# Sheet2.net
KiCad netlist of a schematic drawn in Altium Designer
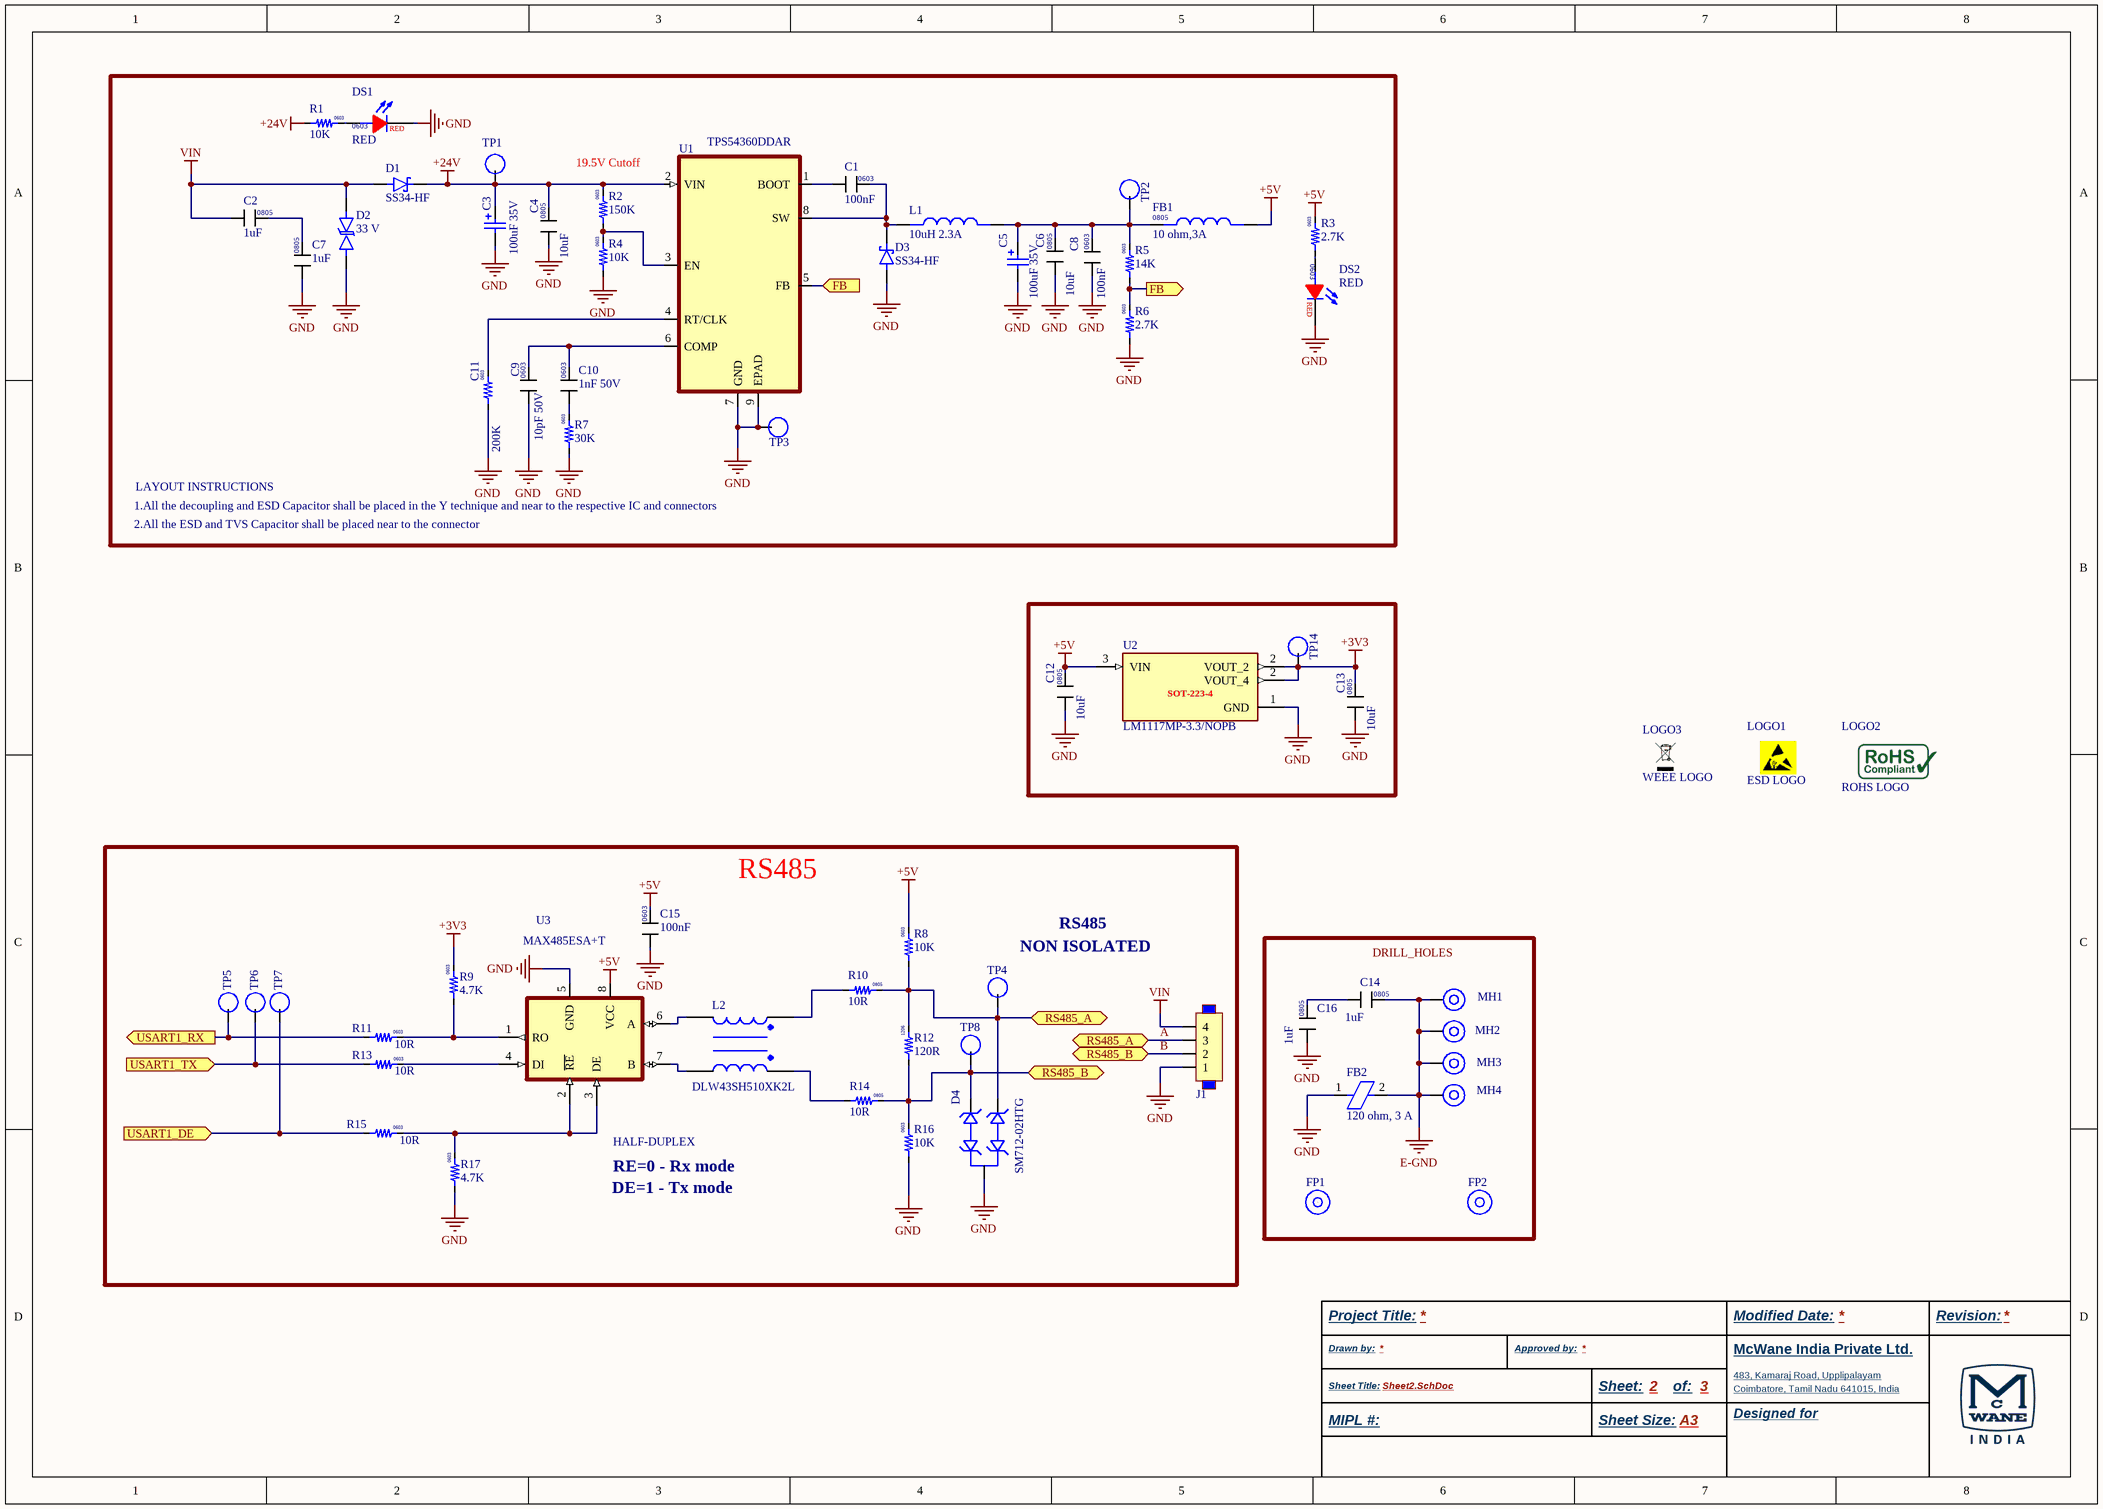
[diagram p0: Sheet2.SchDoc]

(export (version "E")
  (design (tool "Eeschema 10.0.6"))
  (components
    (comp (ref "C1")
      (value "100nF")
      (footprint "CAP_0603")
      (description "SMD Multilayer Ceramic Capacitor, 0.1 µF, 50 V, 0603 [1608 Metric], ± 10%, X7R")
      (fields
        (field (name "MANUFACTURER PART NUMBER") "CC0603KRX7R9BB104")
        (field (name "LCSC PART") "C14663")
      )
      (libsource (lib "Passive_Components") (part "C0603-0.1uF 50V-MLCC"))
    )
    (comp (ref "C2")
      (value "1uF")
      (footprint "CAP_0805")
      (description "SMD Multilayer Ceramic Capacitor, 1 µF, 50 V, 0805 [2012 Metric], ± 10%, X7R, -55 °C")
      (fields
        (field (name "MANUFACTURER PART NUMBER") "CC0805KKX7R9BB105")
        (field (name "LCSC PART") "C91185")
      )
      (libsource (lib "Passive_Components") (part "C0805-1uF 50V-MLCC"))
    )
    (comp (ref "C3")
      (value "100uF 35V")
      (footprint "CAP_ELE_AL_6.3X7.7")
      (description "SMD Aluminium Electrolytic Capacitor, Radial Can - SMD, 100 µF, 35 V, 2000 hours @ 105°C, Polar")
      (fields (field (name "MANUFACTURER PART NUMBER") "MCVVT035M101EA6L"))
      (libsource (lib "Passive_Components") (part "CAP_SMD_100uF_35V"))
    )
    (comp (ref "C4")
      (value "10uF")
      (footprint "CAP_0805")
      (description "SMD Multilayer Ceramic Capacitor, 10 µF, 50 V, 0805 [2012 Metric], ± 10%, X5R")
      (fields
        (field (name "MANUFACTURER PART NUMBER") "CC0805KKX5R9BB106")
        (field (name "LCSC PART") "C440198")
      )
      (libsource (lib "Passive_Components") (part "C0805-10uF 50V-MLCC"))
    )
    (comp (ref "C5")
      (value "100uF 35V")
      (footprint "CAP_ELE_AL_6.3X7.7")
      (description "SMD Aluminium Electrolytic Capacitor, Radial Can - SMD, 100 µF, 35 V, 2000 hours @ 105°C, Polar")
      (fields (field (name "MANUFACTURER PART NUMBER") "MCVVT035M101EA6L"))
      (libsource (lib "Passive_Components") (part "CAP_SMD_100uF_35V"))
    )
    (comp (ref "C6")
      (value "10uF")
      (footprint "CAP_0805")
      (description "SMD Multilayer Ceramic Capacitor, 10 µF, 50 V, 0805 [2012 Metric], ± 10%, X5R")
      (fields
        (field (name "MANUFACTURER PART NUMBER") "CC0805KKX5R9BB106")
        (field (name "LCSC PART") "C440198")
      )
      (libsource (lib "Passive_Components") (part "C0805-10uF 50V-MLCC"))
    )
    (comp (ref "C7")
      (value "1uF")
      (footprint "CAP_0805")
      (description "SMD Multilayer Ceramic Capacitor, 1 µF, 50 V, 0805 [2012 Metric], ± 10%, X7R, -55 °C")
      (fields
        (field (name "MANUFACTURER PART NUMBER") "CC0805KKX7R9BB105")
        (field (name "LCSC PART") "C91185")
      )
      (libsource (lib "Passive_Components") (part "C0805-1uF 50V-MLCC"))
    )
    (comp (ref "C8")
      (value "100nF")
      (footprint "CAP_0603")
      (description "SMD Multilayer Ceramic Capacitor, 0.1 µF, 50 V, 0603 [1608 Metric], ± 10%, X7R")
      (fields
        (field (name "MANUFACTURER PART NUMBER") "CC0603KRX7R9BB104")
        (field (name "LCSC PART") "C14663")
      )
      (libsource (lib "Passive_Components") (part "C0603-0.1uF 50V-MLCC"))
    )
    (comp (ref "C9")
      (value "10pF 50V")
      (footprint "CAP_0603")
      (description "SMD Multilayer Ceramic Capacitor, 10 pF, 50 V, 0603 [1608 Metric], ± 10%, C0G / NP0, -55 °C")
      (fields (field (name "MANUFACTURER PART NUMBER") "CC0603KRNPO9BN100"))
      (libsource (lib "Passive_Components") (part "C0603-10pF 50V-MLCC"))
    )
    (comp (ref "C10")
      (value "1nF 50V")
      (footprint "CAP_0603")
      (description "SMD Multilayer Ceramic Capacitor, 1 nF, 50 V, 0603 [1608 Metric], ± 10%, X7R")
      (fields (field (name "MANUFACTURER PART NUMBER") "CC0603KRX7R9BB102"))
      (libsource (lib "Passive_Components") (part "C0603-1nF 50V-MLCC"))
    )
    (comp (ref "C11")
      (value "200K")
      (footprint "RES_0603")
      (description "SMD Chip Resistor, 200 kohm, ± 1%, 100 mW, 0603 [1608 Metric], Thick Film, General Purpose")
      (fields (field (name "MANUFACTURER PART NUMBER") "RC0603FR-07200KL"))
      (libsource (lib "Passive_Components") (part "R0603-200K-1%"))
    )
    (comp (ref "C12")
      (value "10uF")
      (footprint "CAP_0805")
      (description "SMD Multilayer Ceramic Capacitor, 10 µF, 50 V, 0805 [2012 Metric], ± 10%, X5R")
      (fields
        (field (name "MANUFACTURER PART NUMBER") "CC0805KKX5R9BB106")
        (field (name "LCSC PART") "C440198")
      )
      (libsource (lib "Passive_Components") (part "C0805-10uF 50V-MLCC"))
    )
    (comp (ref "C13")
      (value "10uF")
      (footprint "CAP_0805")
      (description "SMD Multilayer Ceramic Capacitor, 10 µF, 50 V, 0805 [2012 Metric], ± 10%, X5R")
      (fields
        (field (name "MANUFACTURER PART NUMBER") "CC0805KKX5R9BB106")
        (field (name "LCSC PART") "C440198")
      )
      (libsource (lib "Passive_Components") (part "C0805-10uF 50V-MLCC"))
    )
    (comp (ref "C14")
      (value "1uF")
      (footprint "CAP_0805")
      (description "SMD Multilayer Ceramic Capacitor, 1 µF, 50 V, 0805 [2012 Metric], ± 10%, X7R, -55 °C")
      (fields
        (field (name "MANUFACTURER PART NUMBER") "CC0805KKX7R9BB105")
        (field (name "LCSC PART") "C91185")
      )
      (libsource (lib "Passive_Components") (part "C0805-1uF 50V-MLCC"))
    )
    (comp (ref "C15")
      (value "100nF")
      (footprint "CAP_0603")
      (description "SMD Multilayer Ceramic Capacitor, 0.1 µF, 50 V, 0603 [1608 Metric], ± 10%, X7R")
      (fields
        (field (name "MANUFACTURER PART NUMBER") "CC0603KRX7R9BB104")
        (field (name "LCSC PART") "C14663")
      )
      (libsource (lib "Passive_Components") (part "C0603-0.1uF 50V-MLCC"))
    )
    (comp (ref "C16")
      (value "1uF")
      (footprint "CAP_0805")
      (description "SMD Multilayer Ceramic Capacitor, 1 µF, 50 V, 0805 [2012 Metric], ± 10%, X7R, -55 °C")
      (fields
        (field (name "MANUFACTURER PART NUMBER") "CC0805KKX7R9BB105")
        (field (name "LCSC PART") "C91185")
      )
      (libsource (lib "Passive_Components") (part "C0805-1uF 50V-MLCC"))
    )
    (comp (ref "D1")
      (value "SS34-HF")
      (footprint "Diode_SMA_DO-214AC")
      (description "Schottky Rectifier, SSxx Series, 40 V, 3 A, Single, DO-214AC (SMA), 2 Pins, 500 mV")
      (libsource (lib "Active_Components") (part "SS34-HF"))
    )
    (comp (ref "D2")
      (value "33 V")
      (footprint "Diode_SMA_DO-214AC")
      (description "TVS Diode, TRANSZORB SMAJ, Bidirectional, 33 V, 53.3 V, DO-214AC (SMA), 2 Pins")
      (fields (field (name "MANUFACTURER PART NUMBER") "SMAJ33CAHE3_A/H"))
      (libsource (lib "Active_Components") (part "SMAJ33CAHE3_A/H_1"))
    )
    (comp (ref "D3")
      (value "SS34-HF")
      (footprint "Diode_SMA_DO-214AC")
      (description "Schottky Rectifier, SSxx Series, 40 V, 3 A, Single, DO-214AC (SMA), 2 Pins, 500 mV")
      (libsource (lib "Active_Components") (part "SS34-HF"))
    )
    (comp (ref "D4")
      (value "SM712-02HTG")
      (footprint "SOT23")
      (description "ESD Protection Device, 31 V, SOT-23, 3 Pins, 12 V, 600 W, SPA SM712")
      (libsource (lib "Active_Components") (part "ESD_RS485_SM712"))
    )
    (comp (ref "DS1")
      (value "RED")
      (footprint "LED_0603")
      (description "Red LED Indication - Discrete 1.95V 0603 (1608 Metric)")
      (fields
        (field (name "MANUFACTURER PART NUMBER") "19-217/R6C-AL1M2VY/3T")
        (field (name "LCSC PART") "C72044")
      )
      (libsource (lib "Active_Components") (part "19-217/R6C-AL1M2VY/3T"))
    )
    (comp (ref "DS2")
      (value "RED")
      (footprint "LED_0603")
      (description "Red LED Indication - Discrete 1.95V 0603 (1608 Metric)")
      (fields
        (field (name "MANUFACTURER PART NUMBER") "19-217/R6C-AL1M2VY/3T")
        (field (name "LCSC PART") "C72044")
      )
      (libsource (lib "Active_Components") (part "19-217/R6C-AL1M2VY/3T"))
    )
    (comp (ref "FB1")
      (value "10 ohm,3A")
      (footprint "IND_0805")
      (description "10 Ohms @ 100 MHz 1 Signal Line Ferrite Bead 0805 (2012 Metric) 3A 25mOhm")
      (fields (field (name "MANUFACTURER PART NUMBER") "742792011"))
      (libsource (lib "Passive_Components") (part "IND_0805"))
    )
    (comp (ref "FB2")
      (value "120 ohm, 3 A")
      (footprint "IND_1206")
      (description "Ferrite Bead, 1206 [3216 Metric], 120 ohm, 3 A, WE-CBF, 0.03 ohm, ± 25%")
      (fields (field (name "MANUFACTURER PART NUMBER") "742792113"))
      (libsource (lib "Passive_Components") (part "742792113"))
    )
    (comp (ref "FP1")
      (value "Fiducial_Point")
      (footprint "Fiducial_Point")
      (libsource (lib "CONNECTOR") (part "Fiducial_Point"))
    )
    (comp (ref "FP2")
      (value "Fiducial_Point")
      (footprint "Fiducial_Point")
      (libsource (lib "CONNECTOR") (part "Fiducial_Point"))
    )
    (comp (ref "J1")
      (value "WAGO250 104")
      (footprint "WAGO250_104")
      (description "4 Position Wire to Board Terminal Block 45° (135°) Angle with Board 0.138\" (3.50mm) Through Hole")
      (fields (field (name "MANUFACTURER PART NUMBER") "250-104/000-012"))
      (libsource (lib "CONNECTOR") (part "WAGO250_104"))
    )
    (comp (ref "L1")
      (value "10uH 2.3A")
      (footprint "IND_SMD_7X7X5")
      (description "10 µH Unshielded Inductor 2.3 A 70mOhm Max Nonstandard")
      (fields (field (name "MANUFACTURER PART NUMBER") "CD75NP-100KC") (field (name "LCSC PART") "C2454030"))
      (libsource (lib "Passive_Components") (part "IND_10uH_2.3A"))
    )
    (comp (ref "L2")
      (value "DLW43SH510XK2L")
      (footprint "IND_CMC_SMD_4.5X3.2X2.6mm")
      (description "51 µH @ 1 MHz 2 Line Common Mode Choke Surface Mount 230mA DCR 1Ohm")
      (libsource (lib "Passive_Components") (part "DLW43SH510XK2L"))
    )
    (comp (ref "LOGO1")
      (value "ESD LOGO")
      (footprint "ESD_LOGO")
      (libsource (lib "CONNECTOR") (part "ESD_LOGO"))
    )
    (comp (ref "LOGO2")
      (value "ROHS LOGO")
      (footprint "ROHS_LOGO")
      (libsource (lib "CONNECTOR") (part "ROHS_LOGO"))
    )
    (comp (ref "LOGO3")
      (value "WEEE LOGO")
      (footprint "EWASTE_LOGO")
      (libsource (lib "CONNECTOR") (part "WEEE_LOGO"))
    )
    (comp (ref "MH1")
      (value "MOUNT_HOLE_4mm")
      (footprint "MOUNT_HOLE_4mm")
      (libsource (lib "CONNECTOR") (part "MOUNT_HOLE_4mm"))
    )
    (comp (ref "MH2")
      (value "MOUNT_HOLE_4mm")
      (footprint "MOUNT_HOLE_4mm")
      (libsource (lib "CONNECTOR") (part "MOUNT_HOLE_4mm"))
    )
    (comp (ref "MH3")
      (value "MOUNT_HOLE_4mm")
      (footprint "MOUNT_HOLE_4mm")
      (libsource (lib "CONNECTOR") (part "MOUNT_HOLE_4mm"))
    )
    (comp (ref "MH4")
      (value "MOUNT_HOLE_4mm")
      (footprint "MOUNT_HOLE_4mm")
      (libsource (lib "CONNECTOR") (part "MOUNT_HOLE_4mm"))
    )
    (comp (ref "R1")
      (value "10K")
      (footprint "RES_0603")
      (description "SMD Chip Resistor, 10 kohm, ± 1%, 100 mW, 0603 [1608 Metric], Thick Film, General Purpose")
      (fields (field (name "MANUFACTURER PART NUMBER") "RC0603FR-0710KL") (field (name "LCSC PART") "C98220"))
      (libsource (lib "Passive_Components") (part "R0603-10K-1%"))
    )
    (comp (ref "R2")
      (value "150K")
      (footprint "RES_0603")
      (description "SMD Chip Resistor, 150 kohm, ± 1%, 100 mW, 0603 [1608 Metric], Thick Film, General Purpose")
      (fields (field (name "MANUFACTURER PART NUMBER") "RC0603FR-07150KL"))
      (libsource (lib "Passive_Components") (part "R0603-150K-1%"))
    )
    (comp (ref "R3")
      (value "2.7K")
      (footprint "RES_0603")
      (description "SMD Chip Resistor, 2.7 kohm, ± 1%, 100 mW, 0603 [1608 Metric], Thick Film, General Purpose")
      (fields (field (name "MANUFACTURER PART NUMBER") "RC0603FR-072K7L"))
      (libsource (lib "Passive_Components") (part "R0603-2.7K-1%"))
    )
    (comp (ref "R4")
      (value "10K")
      (footprint "RES_0603")
      (description "SMD Chip Resistor, 10 kohm, ± 1%, 100 mW, 0603 [1608 Metric], Thick Film, General Purpose")
      (fields (field (name "MANUFACTURER PART NUMBER") "RC0603FR-0710KL") (field (name "LCSC PART") "C98220"))
      (libsource (lib "Passive_Components") (part "R0603-10K-1%"))
    )
    (comp (ref "R5")
      (value "14K")
      (footprint "RES_0603")
      (description "SMD Chip Resistor, 14 kohm, ± 1%, 100 mW, 0603 [1608 Metric], Thick Film, General Purpose")
      (fields (field (name "MANUFACTURER PART NUMBER") "RC0603FR-0714KL"))
      (libsource (lib "Passive_Components") (part "R0603-14K-1%"))
    )
    (comp (ref "R6")
      (value "2.7K")
      (footprint "RES_0603")
      (description "SMD Chip Resistor, 2.7 kohm, ± 1%, 100 mW, 0603 [1608 Metric], Thick Film, General Purpose")
      (fields (field (name "MANUFACTURER PART NUMBER") "RC0603FR-072K7L"))
      (libsource (lib "Passive_Components") (part "R0603-2.7K-1%"))
    )
    (comp (ref "R7")
      (value "30K")
      (footprint "RES_0603")
      (description "SMD Chip Resistor, 30 kohm, ± 1%, 100 mW, 0603 [1608 Metric], Thick Film, General Purpose")
      (fields (field (name "MANUFACTURER PART NUMBER") "RC0603FR-0730KL"))
      (libsource (lib "Passive_Components") (part "R0603-30K-1%"))
    )
    (comp (ref "R8")
      (value "10K")
      (footprint "RES_0603")
      (description "SMD Chip Resistor, 10 kohm, ± 1%, 100 mW, 0603 [1608 Metric], Thick Film, General Purpose")
      (fields (field (name "MANUFACTURER PART NUMBER") "RC0603FR-0710KL") (field (name "LCSC PART") "C98220"))
      (libsource (lib "Passive_Components") (part "R0603-10K-1%"))
    )
    (comp (ref "R9")
      (value "4.7K")
      (footprint "RES_0603")
      (description "SMD Chip Resistor, 4.7 kohm, ± 1%, 100 mW, 0603 [1608 Metric], Thick Film, General Purpose")
      (fields (field (name "MANUFACTURER PART NUMBER") "RC0603FR-074K7L."))
      (libsource (lib "Passive_Components") (part "R0603-4.7K-1%"))
    )
    (comp (ref "R10")
      (value "10R")
      (footprint "RES_0805")
      (description "SMD Chip Resistor, 10 ohm, ± 1%, 125 mW, 0805 [2012 Metric], Thick Film, General Purpose")
      (fields (field (name "MANUFACTURER PART NUMBER") "RC0805FR-0710RL") (field (name "LCSC PART") "C96347"))
      (libsource (lib "Passive_Components") (part "R0805-10R-1%"))
    )
    (comp (ref "R11")
      (value "10R")
      (footprint "RES_0603")
      (description "SMD Chip Resistor, 10 ohm, ± 1%, 100 mW, 0603 [1608 Metric], Thick Film, General Purpose")
      (fields
        (field (name "MANUFACTURER PART NUMBER") "RC0603FR-0710RL")
        (field (name "LCSC PART") "C109318")
      )
      (libsource (lib "Passive_Components") (part "R0603-10E-1%"))
    )
    (comp (ref "R12")
      (value "120R")
      (footprint "RES_1206")
      (description "SMD Chip Resistor, 120 ohm, ± 1%, 250 mW, 1206 [3216 Metric], Thick Film, General Purpose")
      (fields
        (field (name "MANUFACTURER PART NUMBER") "RC1206FR-07120RL")
        (field (name "LCSC PART") "C114928")
      )
      (libsource (lib "Passive_Components") (part "R1206-120E-1%"))
    )
    (comp (ref "R13")
      (value "10R")
      (footprint "RES_0603")
      (description "SMD Chip Resistor, 10 ohm, ± 1%, 100 mW, 0603 [1608 Metric], Thick Film, General Purpose")
      (fields
        (field (name "MANUFACTURER PART NUMBER") "RC0603FR-0710RL")
        (field (name "LCSC PART") "C109318")
      )
      (libsource (lib "Passive_Components") (part "R0603-10E-1%"))
    )
    (comp (ref "R14")
      (value "10R")
      (footprint "RES_0805")
      (description "SMD Chip Resistor, 10 ohm, ± 1%, 125 mW, 0805 [2012 Metric], Thick Film, General Purpose")
      (fields (field (name "MANUFACTURER PART NUMBER") "RC0805FR-0710RL") (field (name "LCSC PART") "C96347"))
      (libsource (lib "Passive_Components") (part "R0805-10R-1%"))
    )
    (comp (ref "R15")
      (value "10R")
      (footprint "RES_0603")
      (description "SMD Chip Resistor, 10 ohm, ± 1%, 100 mW, 0603 [1608 Metric], Thick Film, General Purpose")
      (fields
        (field (name "MANUFACTURER PART NUMBER") "RC0603FR-0710RL")
        (field (name "LCSC PART") "C109318")
      )
      (libsource (lib "Passive_Components") (part "R0603-10E-1%"))
    )
    (comp (ref "R16")
      (value "10K")
      (footprint "RES_0603")
      (description "SMD Chip Resistor, 10 kohm, ± 1%, 100 mW, 0603 [1608 Metric], Thick Film, General Purpose")
      (fields (field (name "MANUFACTURER PART NUMBER") "RC0603FR-0710KL") (field (name "LCSC PART") "C98220"))
      (libsource (lib "Passive_Components") (part "R0603-10K-1%"))
    )
    (comp (ref "R17")
      (value "4.7K")
      (footprint "RES_0603")
      (description "SMD Chip Resistor, 4.7 kohm, ± 1%, 100 mW, 0603 [1608 Metric], Thick Film, General Purpose")
      (fields (field (name "MANUFACTURER PART NUMBER") "RC0603FR-074K7L."))
      (libsource (lib "Passive_Components") (part "R0603-4.7K-1%"))
    )
    (comp (ref "TP1")
      (value "TP")
      (footprint "TEST_POINT_SMD")
      (libsource (lib "") (part "TEST_POINT_SMD_1"))
    )
    (comp (ref "TP2")
      (value "TP")
      (footprint "TEST_POINT_SMD")
      (libsource (lib "") (part "TEST_POINT_SMD_1"))
    )
    (comp (ref "TP3")
      (value "TP")
      (footprint "TEST_POINT_SMD")
      (libsource (lib "") (part "TEST_POINT_SMD_1"))
    )
    (comp (ref "TP4")
      (value "TEST_POINT_SMD")
      (footprint "TEST_POINT_SMD")
      (libsource (lib "CONNECTOR") (part "TEST_POINT_SMD"))
    )
    (comp (ref "TP5")
      (value "TEST_POINT_SMD")
      (footprint "TEST_POINT_SMD")
      (libsource (lib "CONNECTOR") (part "TEST_POINT_SMD"))
    )
    (comp (ref "TP6")
      (value "TEST_POINT_SMD")
      (footprint "TEST_POINT_SMD")
      (libsource (lib "CONNECTOR") (part "TEST_POINT_SMD"))
    )
    (comp (ref "TP7")
      (value "TEST_POINT_SMD")
      (footprint "TEST_POINT_SMD")
      (libsource (lib "CONNECTOR") (part "TEST_POINT_SMD"))
    )
    (comp (ref "TP8")
      (value "TEST_POINT_SMD")
      (footprint "TEST_POINT_SMD")
      (libsource (lib "CONNECTOR") (part "TEST_POINT_SMD"))
    )
    (comp (ref "TP14")
      (value "TP")
      (footprint "TEST_POINT_SMD")
      (libsource (lib "") (part "TEST_POINT_SMD_1"))
    )
    (comp (ref "U1")
      (value "TPS54360DDAR")
      (footprint "SOP127P600X175-9N")
      (libsource (lib "Active_Components") (part "TPS54360DDAR"))
    )
    (comp (ref "U2")
      (value "LM1117MP-3.3/NOPB")
      (footprint "SOT-223")
      (description "Fixed LDO Voltage Regulator, 15V in, 1.2V Dropout, 3.3V/800mA out, SOT-223-4")
      (fields (field (name "LCSC PART") "C79401"))
      (libsource (lib "Active_Components") (part "LM1117IMPX-3.3/NOPB"))
    )
    (comp (ref "U3")
      (value "MAX485ESA+T")
      (footprint "SOIC-8N")
      (description "Transceiver RS422, RS485, 4.75V-5.25V supply, 1 Driver, NSOIC-8")
      (fields (field (name "MANUFACTURER PART NUMBER") "MAX487ESA+T"))
      (libsource (lib "Active_Components") (part "MAX487ESA+T"))
    )
  )
  (nets
    (net (code "1") (name "+3V3") (class "Default")
      (node (ref "C13") (pin "2") (pinfunction "2_2") (pintype "passive"))
      (node (ref "R9") (pin "2") (pinfunction "2_2") (pintype "passive"))
      (node (ref "TP14") (pin "1") (pinfunction "1_1") (pintype "bidirectional"))
      (node (ref "U2") (pin "2") (pinfunction "VOUT_2_2") (pintype "output"))
    )
    (net (code "2") (name "+5V") (class "Default")
      (node (ref "C12") (pin "2") (pinfunction "2_2") (pintype "passive"))
      (node (ref "C15") (pin "2") (pinfunction "2_2") (pintype "passive"))
      (node (ref "FB1") (pin "2") (pinfunction "2_2") (pintype "passive"))
      (node (ref "R3") (pin "2") (pinfunction "2_2") (pintype "passive"))
      (node (ref "R8") (pin "2") (pinfunction "2_2") (pintype "passive"))
      (node (ref "U2") (pin "3") (pinfunction "VIN_3") (pintype "input"))
      (node (ref "U3") (pin "8") (pinfunction "VCC_8") (pintype "power_in"))
    )
    (net (code "3") (name "+24V") (class "Default")
      (node (ref "C3") (pin "2") (pinfunction "P_2") (pintype "passive"))
      (node (ref "C4") (pin "2") (pinfunction "2_2") (pintype "passive"))
      (node (ref "D1") (pin "C") (pinfunction "C_C") (pintype "passive"))
      (node (ref "R1") (pin "1") (pinfunction "1_1") (pintype "passive"))
      (node (ref "R2") (pin "2") (pinfunction "2_2") (pintype "passive"))
      (node (ref "TP1") (pin "1") (pinfunction "1_1") (pintype "bidirectional"))
      (node (ref "U1") (pin "2") (pinfunction "VIN_2") (pintype "input"))
    )
    (net (code "4") (name "/A") (class "Default")
      (node (ref "D4") (pin "2") (pinfunction "IO2_2") (pintype "bidirectional"))
      (node (ref "J1") (pin "3") (pinfunction "3_3") (pintype "passive"))
      (node (ref "R10") (pin "2") (pinfunction "2_2") (pintype "passive"))
      (node (ref "R12") (pin "2") (pinfunction "2_2") (pintype "passive"))
      (node (ref "R8") (pin "1") (pinfunction "1_1") (pintype "passive"))
      (node (ref "TP4") (pin "1") (pinfunction "1_1") (pintype "bidirectional"))
    )
    (net (code "5") (name "/B") (class "Default")
      (node (ref "D4") (pin "1") (pinfunction "IO1_1") (pintype "bidirectional"))
      (node (ref "J1") (pin "2") (pinfunction "2_2") (pintype "passive"))
      (node (ref "R12") (pin "1") (pinfunction "1_1") (pintype "passive"))
      (node (ref "R14") (pin "2") (pinfunction "2_2") (pintype "passive"))
      (node (ref "R16") (pin "2") (pinfunction "2_2") (pintype "passive"))
      (node (ref "TP8") (pin "1") (pinfunction "1_1") (pintype "bidirectional"))
    )
    (net (code "7") (name "/FB") (class "Default")
      (node (ref "R5") (pin "1") (pinfunction "1_1") (pintype "passive"))
      (node (ref "R6") (pin "2") (pinfunction "2_2") (pintype "passive"))
      (node (ref "U1") (pin "5") (pinfunction "FB_5") (pintype "bidirectional"))
    )
    (net (code "8") (name "/USART1_DE") (class "Default")
      (node (ref "R15") (pin "1") (pinfunction "1_1") (pintype "passive"))
      (node (ref "TP7") (pin "1") (pinfunction "1_1") (pintype "bidirectional"))
    )
    (net (code "9") (name "/USART1_RX") (class "Default")
      (node (ref "R11") (pin "1") (pinfunction "1_1") (pintype "passive"))
      (node (ref "TP5") (pin "1") (pinfunction "1_1") (pintype "bidirectional"))
    )
    (net (code "10") (name "/USART1_TX") (class "Default")
      (node (ref "R13") (pin "1") (pinfunction "1_1") (pintype "passive"))
      (node (ref "TP6") (pin "1") (pinfunction "1_1") (pintype "bidirectional"))
    )
    (net (code "11") (name "E-GND") (class "Default")
      (node (ref "C14") (pin "2") (pinfunction "2_2") (pintype "passive"))
      (node (ref "FB2") (pin "2") (pinfunction "2_2") (pintype "passive"))
      (node (ref "MH1") (pin "1") (pinfunction "1_1") (pintype "passive"))
      (node (ref "MH2") (pin "1") (pinfunction "1_1") (pintype "passive"))
      (node (ref "MH3") (pin "1") (pinfunction "1_1") (pintype "passive"))
      (node (ref "MH4") (pin "1") (pinfunction "1_1") (pintype "passive"))
    )
    (net (code "12") (name "GND") (class "Default")
      (node (ref "C11") (pin "1") (pinfunction "1_1") (pintype "passive"))
      (node (ref "C12") (pin "1") (pinfunction "1_1") (pintype "passive"))
      (node (ref "C13") (pin "1") (pinfunction "1_1") (pintype "passive"))
      (node (ref "C15") (pin "1") (pinfunction "1_1") (pintype "passive"))
      (node (ref "C16") (pin "1") (pinfunction "1_1") (pintype "passive"))
      (node (ref "C3") (pin "1") (pinfunction "N_1") (pintype "passive"))
      (node (ref "C4") (pin "1") (pinfunction "1_1") (pintype "passive"))
      (node (ref "C5") (pin "1") (pinfunction "N_1") (pintype "passive"))
      (node (ref "C6") (pin "1") (pinfunction "1_1") (pintype "passive"))
      (node (ref "C7") (pin "1") (pinfunction "1_1") (pintype "passive"))
      (node (ref "C8") (pin "1") (pinfunction "1_1") (pintype "passive"))
      (node (ref "C9") (pin "1") (pinfunction "1_1") (pintype "passive"))
      (node (ref "D2") (pin "C") (pinfunction "C_C") (pintype "passive"))
      (node (ref "D3") (pin "A") (pinfunction "A_A") (pintype "passive"))
      (node (ref "D4") (pin "3") (pinfunction "GND_3") (pintype "bidirectional"))
      (node (ref "DS1") (pin "C") (pinfunction "C_C") (pintype "passive"))
      (node (ref "DS2") (pin "C") (pinfunction "C_C") (pintype "passive"))
      (node (ref "FB2") (pin "1") (pinfunction "1_1") (pintype "passive"))
      (node (ref "J1") (pin "1") (pinfunction "1_1") (pintype "passive"))
      (node (ref "R16") (pin "1") (pinfunction "1_1") (pintype "passive"))
      (node (ref "R17") (pin "1") (pinfunction "1_1") (pintype "passive"))
      (node (ref "R4") (pin "1") (pinfunction "1_1") (pintype "passive"))
      (node (ref "R6") (pin "1") (pinfunction "1_1") (pintype "passive"))
      (node (ref "R7") (pin "1") (pinfunction "1_1") (pintype "passive"))
      (node (ref "TP3") (pin "1") (pinfunction "1_1") (pintype "bidirectional"))
      (node (ref "U1") (pin "7") (pinfunction "GND_7") (pintype "power_in"))
      (node (ref "U1") (pin "9") (pinfunction "EPAD_9") (pintype "passive"))
      (node (ref "U2") (pin "1") (pinfunction "GND_1") (pintype "power_in"))
      (node (ref "U3") (pin "5") (pinfunction "GND_5") (pintype "passive"))
    )
    (net (code "13") (name "Net-(C2-Pad2)") (class "Default")
      (node (ref "C2") (pin "2") (pinfunction "2_2") (pintype "passive"))
      (node (ref "C7") (pin "2") (pinfunction "2_2") (pintype "passive"))
    )
    (net (code "14") (name "Net-(C5-P)") (class "Default")
      (node (ref "C5") (pin "2") (pinfunction "P_2") (pintype "passive"))
      (node (ref "C6") (pin "2") (pinfunction "2_2") (pintype "passive"))
      (node (ref "C8") (pin "2") (pinfunction "2_2") (pintype "passive"))
      (node (ref "FB1") (pin "1") (pinfunction "1_1") (pintype "passive"))
      (node (ref "L1") (pin "2") (pinfunction "2_2") (pintype "passive"))
      (node (ref "R5") (pin "2") (pinfunction "2_2") (pintype "passive"))
      (node (ref "TP2") (pin "1") (pinfunction "1_1") (pintype "bidirectional"))
    )
    (net (code "15") (name "Net-(C10-Pad1)") (class "Default")
      (node (ref "C10") (pin "1") (pinfunction "1_1") (pintype "passive"))
      (node (ref "R7") (pin "2") (pinfunction "2_2") (pintype "passive"))
    )
    (net (code "16") (name "Net-(C14-Pad1)") (class "Default")
      (node (ref "C14") (pin "1") (pinfunction "1_1") (pintype "passive"))
      (node (ref "C16") (pin "2") (pinfunction "2_2") (pintype "passive"))
    )
    (net (code "17") (name "Net-(DS1-PadA)") (class "Default")
      (node (ref "DS1") (pin "A") (pinfunction "A_A") (pintype "passive"))
      (node (ref "R1") (pin "2") (pinfunction "2_2") (pintype "passive"))
    )
    (net (code "18") (name "Net-(DS2-PadA)") (class "Default")
      (node (ref "DS2") (pin "A") (pinfunction "A_A") (pintype "passive"))
      (node (ref "R3") (pin "1") (pinfunction "1_1") (pintype "passive"))
    )
    (net (code "19") (name "Net-(L2-Pad1)") (class "Default")
      (node (ref "L2") (pin "1") (pinfunction "1_1") (pintype "passive"))
      (node (ref "R14") (pin "1") (pinfunction "1_1") (pintype "passive"))
    )
    (net (code "20") (name "Net-(L2-Pad4)") (class "Default")
      (node (ref "L2") (pin "4") (pinfunction "4_4") (pintype "passive"))
      (node (ref "R10") (pin "1") (pinfunction "1_1") (pintype "passive"))
    )
    (net (code "21") (name "Net-(U1-BOOT)") (class "Default")
      (node (ref "C1") (pin "1") (pinfunction "1_1") (pintype "passive"))
      (node (ref "U1") (pin "1") (pinfunction "BOOT_1") (pintype "bidirectional"))
    )
    (net (code "22") (name "Net-(U1-COMP)") (class "Default")
      (node (ref "C10") (pin "2") (pinfunction "2_2") (pintype "passive"))
      (node (ref "C9") (pin "2") (pinfunction "2_2") (pintype "passive"))
      (node (ref "U1") (pin "6") (pinfunction "COMP_6") (pintype "bidirectional"))
    )
    (net (code "23") (name "Net-(U1-EN)") (class "Default")
      (node (ref "R2") (pin "1") (pinfunction "1_1") (pintype "passive"))
      (node (ref "R4") (pin "2") (pinfunction "2_2") (pintype "passive"))
      (node (ref "U1") (pin "3") (pinfunction "EN_3") (pintype "bidirectional"))
    )
    (net (code "24") (name "Net-(U1-RT{slash}CLK)") (class "Default")
      (node (ref "C11") (pin "2") (pinfunction "2_2") (pintype "passive"))
      (node (ref "U1") (pin "4") (pinfunction "RT/CLK_4") (pintype "bidirectional"))
    )
    (net (code "25") (name "Net-(U1-SW)") (class "Default")
      (node (ref "C1") (pin "2") (pinfunction "2_2") (pintype "passive"))
      (node (ref "D3") (pin "C") (pinfunction "C_C") (pintype "passive"))
      (node (ref "L1") (pin "1") (pinfunction "1_1") (pintype "passive"))
      (node (ref "U1") (pin "8") (pinfunction "SW_8") (pintype "bidirectional"))
    )
    (net (code "26") (name "Net-(U3-A)") (class "Default")
      (node (ref "L2") (pin "3") (pinfunction "3_3") (pintype "passive"))
      (node (ref "U3") (pin "6") (pinfunction "A_6") (pintype "bidirectional"))
    )
    (net (code "27") (name "Net-(U3-B)") (class "Default")
      (node (ref "L2") (pin "2") (pinfunction "2_2") (pintype "passive"))
      (node (ref "U3") (pin "7") (pinfunction "B_7") (pintype "bidirectional"))
    )
    (net (code "28") (name "Net-(U3-DE)") (class "Default")
      (node (ref "R15") (pin "2") (pinfunction "2_2") (pintype "passive"))
      (node (ref "R17") (pin "2") (pinfunction "2_2") (pintype "passive"))
      (node (ref "U3") (pin "2") (pinfunction "~{RE}_2") (pintype "input"))
      (node (ref "U3") (pin "3") (pinfunction "DE_3") (pintype "input"))
    )
    (net (code "29") (name "Net-(U3-DI)") (class "Default")
      (node (ref "R13") (pin "2") (pinfunction "2_2") (pintype "passive"))
      (node (ref "U3") (pin "4") (pinfunction "DI_4") (pintype "input"))
    )
    (net (code "30") (name "Net-(U3-RO)") (class "Default")
      (node (ref "R11") (pin "2") (pinfunction "2_2") (pintype "passive"))
      (node (ref "R9") (pin "1") (pinfunction "1_1") (pintype "passive"))
      (node (ref "U3") (pin "1") (pinfunction "RO_1") (pintype "output"))
    )
    (net (code "31") (name "VIN") (class "Default")
      (node (ref "C2") (pin "1") (pinfunction "1_1") (pintype "passive"))
      (node (ref "D1") (pin "A") (pinfunction "A_A") (pintype "passive"))
      (node (ref "D2") (pin "A") (pinfunction "A_A") (pintype "passive"))
      (node (ref "J1") (pin "4") (pinfunction "4_4") (pintype "passive"))
    )
    (net (code "32") (name "unconnected-(FP1-Pad1)") (class "Default")
      (node (ref "FP1") (pin "1") (pinfunction "1_1") (pintype "passive"))
    )
    (net (code "33") (name "unconnected-(FP2-Pad1)") (class "Default")
      (node (ref "FP2") (pin "1") (pinfunction "1_1") (pintype "passive"))
    )
  )
)
